# multi-pcb-power.net
KiCad netlist of a schematic drawn in EAGLE
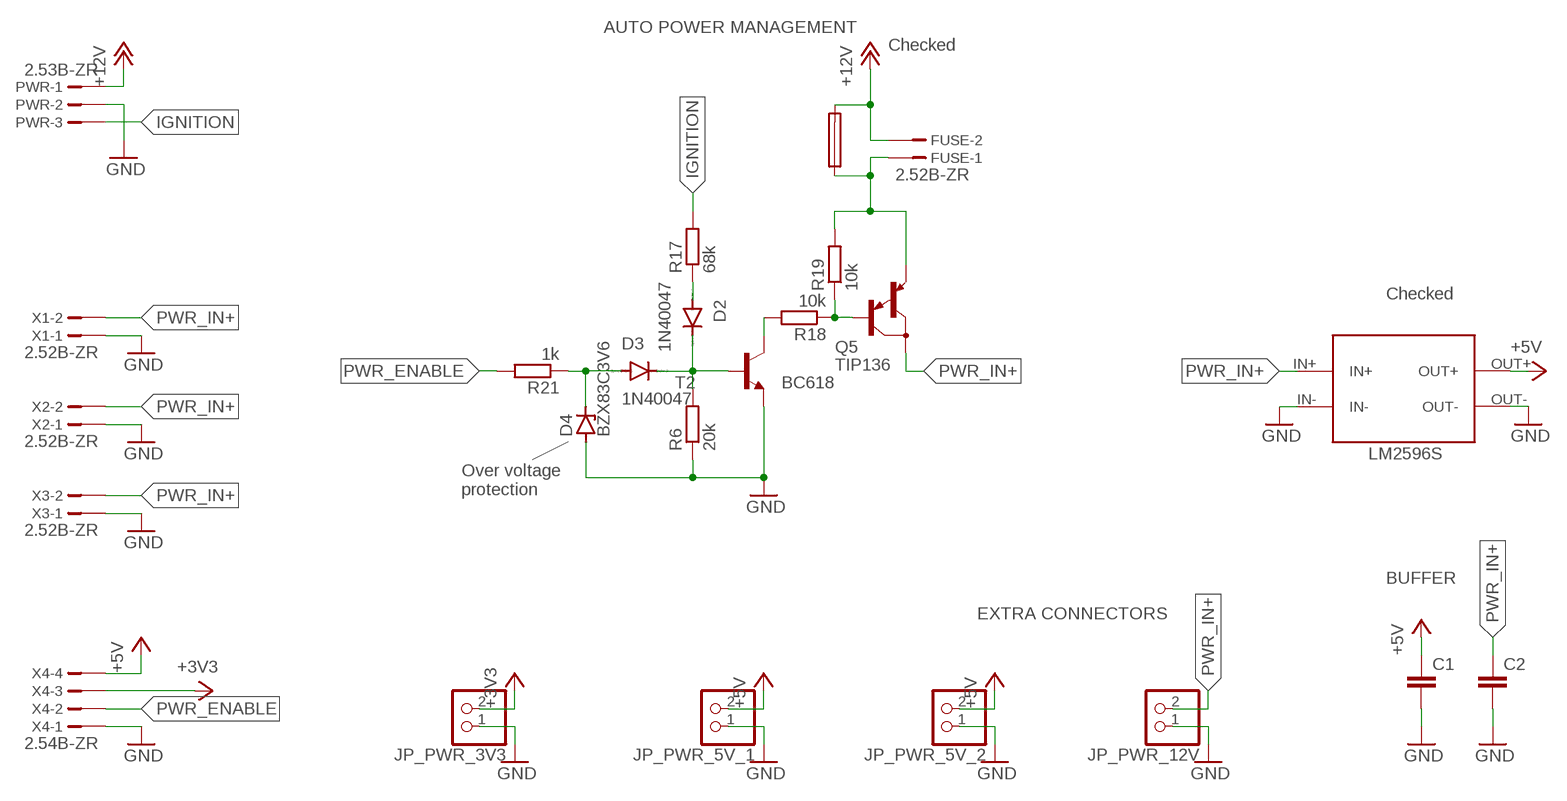
[diagram p0: schematic, sheet 1]

(export (version "E")
  (design (tool "Eeschema 10.0.6"))
  (components
    (comp (ref "C1")
      (value "C-EU050-075X075")
      (footprint "eagle-import:C050-075X075")
      (libsource (lib "eagle-import") (part "C-EU050-075X075"))
    )
    (comp (ref "C2")
      (value "C-EU050-075X075")
      (footprint "eagle-import:C050-075X075")
      (libsource (lib "eagle-import") (part "C-EU050-075X075"))
    )
    (comp (ref "D2")
      (value "1N40047")
      (footprint "eagle-import:DO41-7.6")
      (libsource (lib "eagle-import") (part "1N40047"))
    )
    (comp (ref "D3")
      (value "1N40047")
      (footprint "eagle-import:DO41-7.6")
      (libsource (lib "eagle-import") (part "1N40047"))
    )
    (comp (ref "D4")
      (value "BZX83C3V6")
      (footprint "eagle-import:DO41Z7.6")
      (libsource (lib "eagle-import") (part "BZX857"))
    )
    (comp (ref "FUSE")
      (value "2.52B-ZR")
      (footprint "eagle-import:B2B-ZR2.5")
      (libsource (lib "eagle-import") (part "?2B-ZR2.5"))
    )
    (comp (ref "JP_PWR_3V3")
      (value "PINHD-1X2")
      (footprint "eagle-import:1X02")
      (libsource (lib "eagle-import") (part "PINHD-1X2"))
    )
    (comp (ref "JP_PWR_5V_1")
      (value "PINHD-1X2")
      (footprint "eagle-import:1X02")
      (libsource (lib "eagle-import") (part "PINHD-1X2"))
    )
    (comp (ref "JP_PWR_5V_2")
      (value "PINHD-1X2")
      (footprint "eagle-import:1X02")
      (libsource (lib "eagle-import") (part "PINHD-1X2"))
    )
    (comp (ref "JP_PWR_12V")
      (value "PINHD-1X2")
      (footprint "eagle-import:1X02")
      (libsource (lib "eagle-import") (part "PINHD-1X2"))
    )
    (comp (ref "PWR")
      (value "2.53B-ZR")
      (footprint "eagle-import:B3B-ZR2.5")
      (libsource (lib "eagle-import") (part "?3B-ZR2.5"))
    )
    (comp (ref "Q5")
      (value "TIP136")
      (footprint "eagle-import:TO220")
      (libsource (lib "eagle-import") (part "TIP136"))
    )
    (comp (ref "R6")
      (value "20k")
      (footprint "eagle-import:0207_7")
      (libsource (lib "eagle-import") (part "R-EU_0207/7"))
    )
    (comp (ref "R17")
      (value "68k")
      (footprint "eagle-import:0207_7")
      (libsource (lib "eagle-import") (part "R-EU_0207/7"))
    )
    (comp (ref "R18")
      (value "10k")
      (footprint "eagle-import:0207_7")
      (libsource (lib "eagle-import") (part "R-EU_0207/7"))
    )
    (comp (ref "R19")
      (value "10k")
      (footprint "eagle-import:0207_7")
      (libsource (lib "eagle-import") (part "R-EU_0207/7"))
    )
    (comp (ref "R21")
      (value "1k")
      (footprint "eagle-import:0207_7")
      (libsource (lib "eagle-import") (part "R-EU_0207/7"))
    )
    (comp (ref "T2")
      (value "BC618")
      (footprint "eagle-import:TO92-EBC")
      (libsource (lib "eagle-import") (part "BC618"))
    )
    (comp (ref "U$1")
      (value "FUSE")
      (footprint "eagle-import:FB-5X20")
      (libsource (lib "eagle-import") (part "FUSE"))
    )
    (comp (ref "U$4")
      (value "LM2596S")
      (footprint "eagle-import:LM2596S")
      (libsource (lib "eagle-import") (part "LM2596S"))
    )
    (comp (ref "X1")
      (value "2.52B-ZR")
      (footprint "eagle-import:B2B-ZR2.5")
      (libsource (lib "eagle-import") (part "?2B-ZR2.5"))
    )
    (comp (ref "X2")
      (value "2.52B-ZR")
      (footprint "eagle-import:B2B-ZR2.5")
      (libsource (lib "eagle-import") (part "?2B-ZR2.5"))
    )
    (comp (ref "X3")
      (value "2.52B-ZR")
      (footprint "eagle-import:B2B-ZR2.5")
      (libsource (lib "eagle-import") (part "?2B-ZR2.5"))
    )
    (comp (ref "X4")
      (value "2.54B-ZR")
      (footprint "eagle-import:B4B-ZR2.5")
      (libsource (lib "eagle-import") (part "?4B-ZR2.5"))
    )
  )
  (nets
    (net (code "1") (name "+3V3") (class "Default")
      (node (ref "JP_PWR_3V3") (pin "2") (pinfunction "2_2") (pintype "passive"))
      (node (ref "X4") (pin "3") (pinfunction "1_3") (pintype "passive"))
    )
    (net (code "2") (name "+5V") (class "Default")
      (node (ref "C1") (pin "1") (pinfunction "1_1") (pintype "passive"))
      (node (ref "JP_PWR_5V_1") (pin "2") (pinfunction "2_2") (pintype "passive"))
      (node (ref "JP_PWR_5V_2") (pin "2") (pinfunction "2_2") (pintype "passive"))
      (node (ref "U$4") (pin "OUT+") (pinfunction "OUT+_OUT+") (pintype "bidirectional"))
      (node (ref "X4") (pin "4") (pinfunction "1_4") (pintype "passive"))
    )
    (net (code "3") (name "+12V") (class "Default")
      (node (ref "FUSE") (pin "2") (pinfunction "1_2") (pintype "passive"))
      (node (ref "PWR") (pin "1") (pinfunction "1_1") (pintype "passive"))
      (node (ref "U$1") (pin "P$3") (pinfunction "P$2_P$3") (pintype "passive"))
      (node (ref "U$1") (pin "P$4") (pinfunction "P$2_P$4") (pintype "passive"))
    )
    (net (code "4") (name "GND") (class "Default")
      (node (ref "C1") (pin "2") (pinfunction "2_2") (pintype "passive"))
      (node (ref "C2") (pin "2") (pinfunction "2_2") (pintype "passive"))
      (node (ref "D4") (pin "A") (pinfunction "A_A") (pintype "passive"))
      (node (ref "JP_PWR_12V") (pin "1") (pinfunction "1_1") (pintype "passive"))
      (node (ref "JP_PWR_3V3") (pin "1") (pinfunction "1_1") (pintype "passive"))
      (node (ref "JP_PWR_5V_1") (pin "1") (pinfunction "1_1") (pintype "passive"))
      (node (ref "JP_PWR_5V_2") (pin "1") (pinfunction "1_1") (pintype "passive"))
      (node (ref "PWR") (pin "2") (pinfunction "1_2") (pintype "passive"))
      (node (ref "R6") (pin "1") (pinfunction "1_1") (pintype "passive"))
      (node (ref "T2") (pin "E") (pinfunction "E_E") (pintype "passive"))
      (node (ref "U$4") (pin "IN-") (pinfunction "IN-_IN-") (pintype "bidirectional"))
      (node (ref "U$4") (pin "OUT-") (pinfunction "OUT-_OUT-") (pintype "bidirectional"))
      (node (ref "X1") (pin "1") (pinfunction "1_1") (pintype "passive"))
      (node (ref "X2") (pin "1") (pinfunction "1_1") (pintype "passive"))
      (node (ref "X3") (pin "1") (pinfunction "1_1") (pintype "passive"))
      (node (ref "X4") (pin "1") (pinfunction "1_1") (pintype "passive"))
    )
    (net (code "5") (name "IGNITION") (class "Default")
      (node (ref "PWR") (pin "3") (pinfunction "1_3") (pintype "passive"))
      (node (ref "R17") (pin "2") (pinfunction "2_2") (pintype "passive"))
    )
    (net (code "6") (name "Net-(D2-PadA)") (class "Default")
      (node (ref "D2") (pin "A") (pinfunction "A_A") (pintype "passive"))
      (node (ref "R17") (pin "1") (pinfunction "1_1") (pintype "passive"))
    )
    (net (code "7") (name "Net-(D2-PadC)") (class "Default")
      (node (ref "D2") (pin "C") (pinfunction "C_C") (pintype "passive"))
      (node (ref "D3") (pin "C") (pinfunction "C_C") (pintype "passive"))
      (node (ref "R6") (pin "2") (pinfunction "2_2") (pintype "passive"))
      (node (ref "T2") (pin "B") (pinfunction "B_B") (pintype "passive"))
    )
    (net (code "8") (name "Net-(D3-PadA)") (class "Default")
      (node (ref "D3") (pin "A") (pinfunction "A_A") (pintype "passive"))
      (node (ref "D4") (pin "C") (pinfunction "C_C") (pintype "passive"))
      (node (ref "R21") (pin "1") (pinfunction "1_1") (pintype "passive"))
    )
    (net (code "9") (name "Net-(Q5-B)") (class "Default")
      (node (ref "Q5") (pin "1") (pinfunction "B_1") (pintype "passive"))
      (node (ref "R18") (pin "1") (pinfunction "1_1") (pintype "passive"))
      (node (ref "R19") (pin "1") (pinfunction "1_1") (pintype "passive"))
    )
    (net (code "10") (name "Net-(Q5-E)") (class "Default")
      (node (ref "FUSE") (pin "1") (pinfunction "1_1") (pintype "passive"))
      (node (ref "Q5") (pin "3") (pinfunction "E_3") (pintype "passive"))
      (node (ref "R19") (pin "2") (pinfunction "2_2") (pintype "passive"))
      (node (ref "U$1") (pin "P$1") (pinfunction "P$1_P$1") (pintype "passive"))
      (node (ref "U$1") (pin "P$2") (pinfunction "P$1_P$2") (pintype "passive"))
    )
    (net (code "11") (name "Net-(R18-Pad2)") (class "Default")
      (node (ref "R18") (pin "2") (pinfunction "2_2") (pintype "passive"))
      (node (ref "T2") (pin "C") (pinfunction "C_C") (pintype "passive"))
    )
    (net (code "12") (name "PWR_ENABLE") (class "Default")
      (node (ref "R21") (pin "2") (pinfunction "2_2") (pintype "passive"))
      (node (ref "X4") (pin "2") (pinfunction "1_2") (pintype "passive"))
    )
    (net (code "13") (name "PWR_IN+") (class "Default")
      (node (ref "C2") (pin "1") (pinfunction "1_1") (pintype "passive"))
      (node (ref "JP_PWR_12V") (pin "2") (pinfunction "2_2") (pintype "passive"))
      (node (ref "Q5") (pin "2") (pinfunction "C_2") (pintype "passive"))
      (node (ref "U$4") (pin "IN+") (pinfunction "IN+_IN+") (pintype "bidirectional"))
      (node (ref "X1") (pin "2") (pinfunction "1_2") (pintype "passive"))
      (node (ref "X2") (pin "2") (pinfunction "1_2") (pintype "passive"))
      (node (ref "X3") (pin "2") (pinfunction "1_2") (pintype "passive"))
    )
  )
)
